# 9AxisCombo.net
KiCad netlist of a schematic drawn in EAGLE
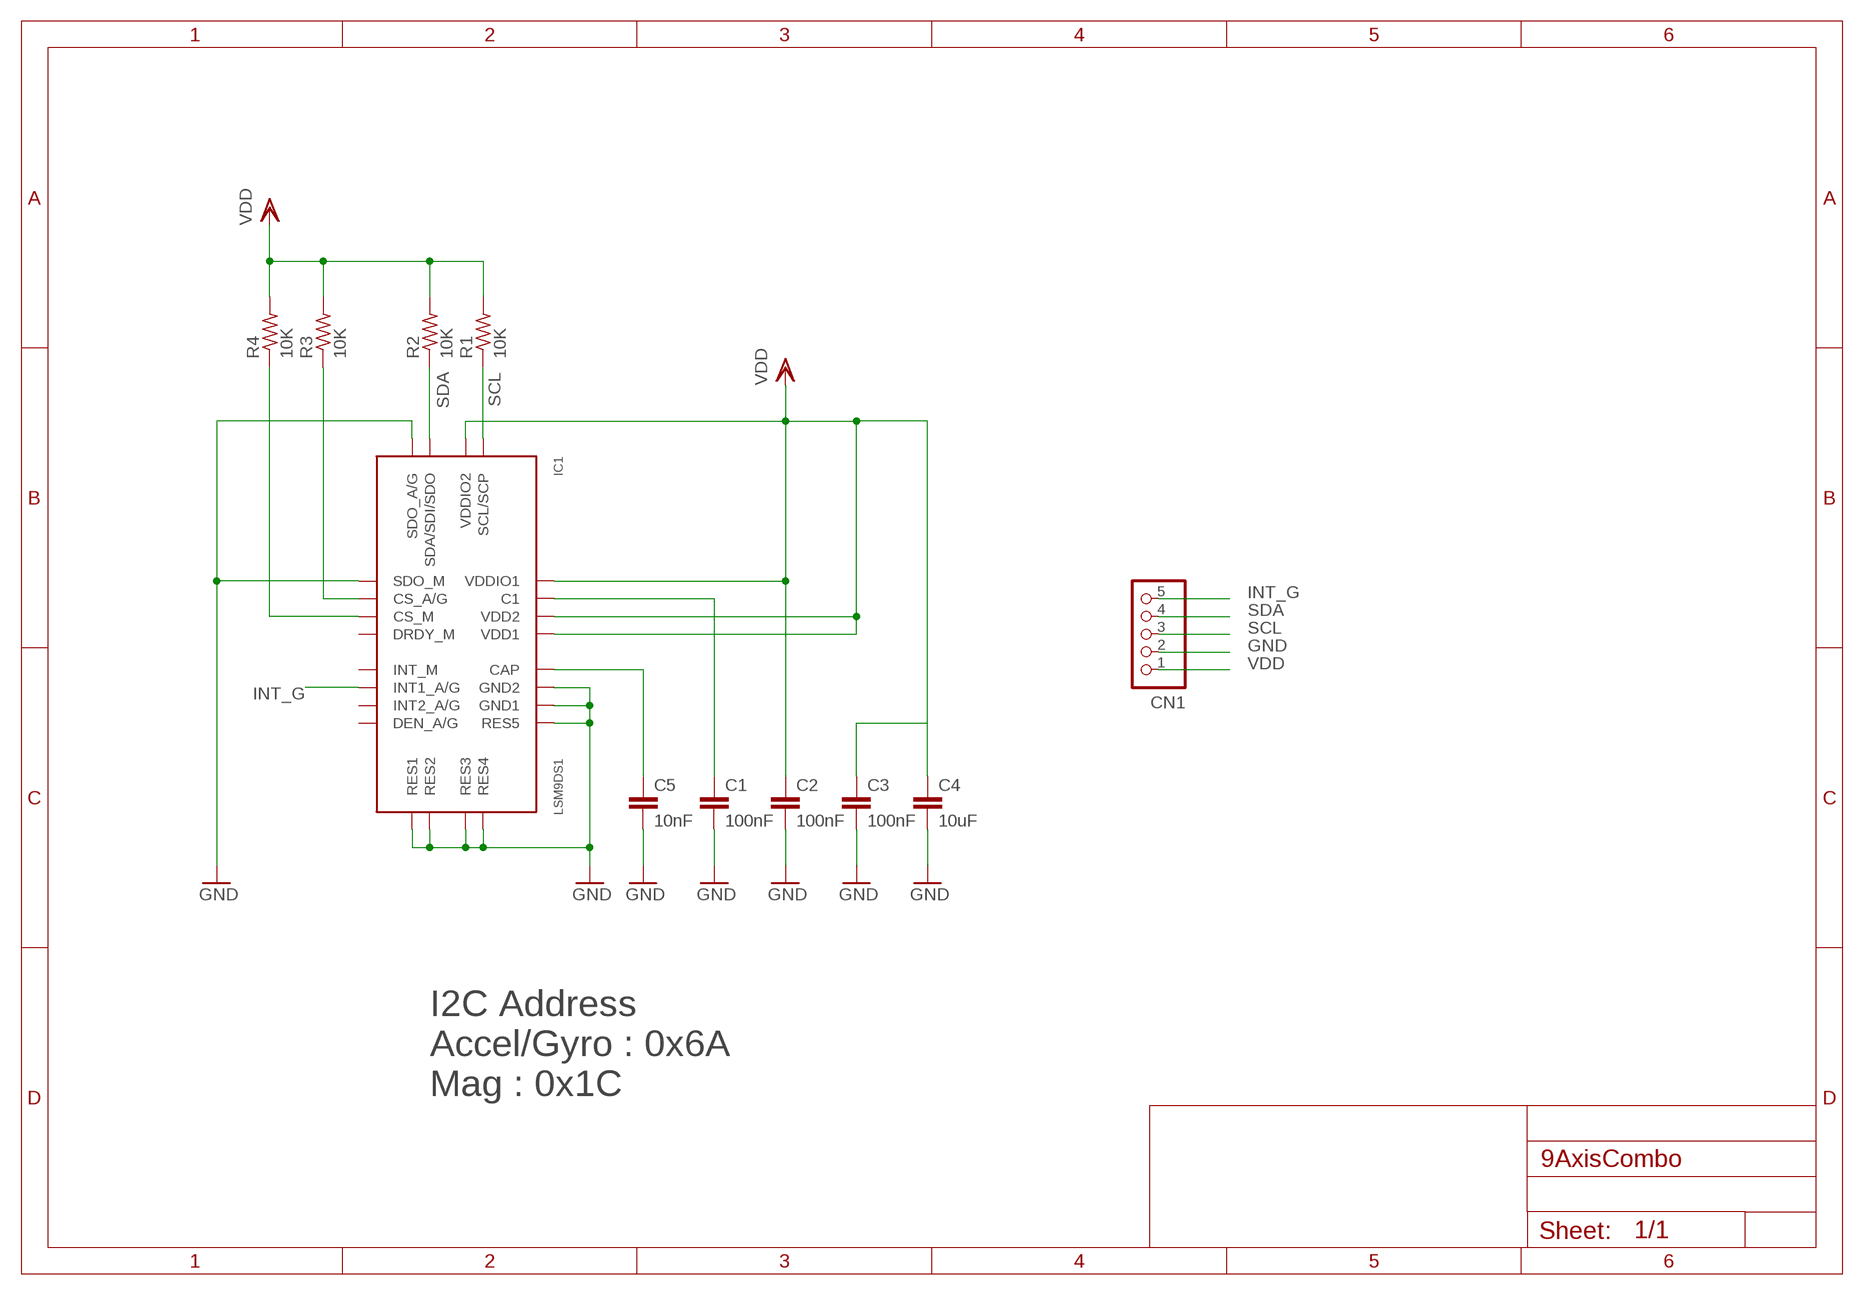
[diagram p0: schematic, sheet 1]

(export (version "E")
  (design (tool "Eeschema 10.0.6"))
  (components
    (comp (ref "C1")
      (value "100nF")
      (footprint "eagle-import:C0603")
      (libsource (lib "eagle-import") (part "C-EUC0603"))
    )
    (comp (ref "C2")
      (value "100nF")
      (footprint "eagle-import:C0603")
      (libsource (lib "eagle-import") (part "C-EUC0603"))
    )
    (comp (ref "C3")
      (value "100nF")
      (footprint "eagle-import:C0603")
      (libsource (lib "eagle-import") (part "C-EUC0603"))
    )
    (comp (ref "C4")
      (value "10uF")
      (footprint "eagle-import:C0603")
      (libsource (lib "eagle-import") (part "C-EUC0603"))
    )
    (comp (ref "C5")
      (value "10nF")
      (footprint "eagle-import:C0603")
      (libsource (lib "eagle-import") (part "C-EUC0603"))
    )
    (comp (ref "CN1")
      (value "B5B-PH-K-S")
      (footprint "eagle-import:B5B-PH-K-S")
      (libsource (lib "eagle-import") (part "B5B-PH-K-S"))
    )
    (comp (ref "IC1")
      (value "LSM9DS1")
      (footprint "eagle-import:LGA-24L")
      (libsource (lib "eagle-import") (part "LSM9DS1"))
    )
    (comp (ref "R1")
      (value "10K")
      (footprint "eagle-import:R0603")
      (libsource (lib "eagle-import") (part "R-US_R0603"))
    )
    (comp (ref "R2")
      (value "10K")
      (footprint "eagle-import:R0603")
      (libsource (lib "eagle-import") (part "R-US_R0603"))
    )
    (comp (ref "R3")
      (value "10K")
      (footprint "eagle-import:R0603")
      (libsource (lib "eagle-import") (part "R-US_R0603"))
    )
    (comp (ref "R4")
      (value "10K")
      (footprint "eagle-import:R0603")
      (libsource (lib "eagle-import") (part "R-US_R0603"))
    )
  )
  (nets
    (net (code "1") (name "/INT_G") (class "Default")
      (node (ref "CN1") (pin "5") (pinfunction "5_5") (pintype "passive"))
      (node (ref "IC1") (pin "11") (pinfunction "INT1_A/G_11") (pintype "bidirectional"))
    )
    (net (code "2") (name "/SCL") (class "Default")
      (node (ref "CN1") (pin "3") (pinfunction "3_3") (pintype "passive"))
      (node (ref "IC1") (pin "2") (pinfunction "SCL/SCP_2") (pintype "bidirectional"))
      (node (ref "R1") (pin "1") (pinfunction "1_1") (pintype "passive"))
    )
    (net (code "3") (name "/SDA") (class "Default")
      (node (ref "CN1") (pin "4") (pinfunction "4_4") (pintype "passive"))
      (node (ref "IC1") (pin "4") (pinfunction "SDA/SDI/SDO_4") (pintype "bidirectional"))
      (node (ref "R2") (pin "1") (pinfunction "1_1") (pintype "passive"))
    )
    (net (code "4") (name "GND") (class "Default")
      (node (ref "C1") (pin "2") (pinfunction "2_2") (pintype "passive"))
      (node (ref "C2") (pin "2") (pinfunction "2_2") (pintype "passive"))
      (node (ref "C3") (pin "2") (pinfunction "2_2") (pintype "passive"))
      (node (ref "C4") (pin "2") (pinfunction "2_2") (pintype "passive"))
      (node (ref "C5") (pin "2") (pinfunction "2_2") (pintype "passive"))
      (node (ref "CN1") (pin "2") (pinfunction "2_2") (pintype "passive"))
      (node (ref "IC1") (pin "14") (pinfunction "RES1_14") (pintype "bidirectional"))
      (node (ref "IC1") (pin "15") (pinfunction "RES2_15") (pintype "bidirectional"))
      (node (ref "IC1") (pin "16") (pinfunction "RES3_16") (pintype "bidirectional"))
      (node (ref "IC1") (pin "17") (pinfunction "RES4_17") (pintype "bidirectional"))
      (node (ref "IC1") (pin "18") (pinfunction "RES5_18") (pintype "bidirectional"))
      (node (ref "IC1") (pin "19") (pinfunction "GND1_19") (pintype "power_in"))
      (node (ref "IC1") (pin "20") (pinfunction "GND2_20") (pintype "power_in"))
      (node (ref "IC1") (pin "5") (pinfunction "SDO_A/G_5") (pintype "bidirectional"))
      (node (ref "IC1") (pin "6") (pinfunction "SDO_M_6") (pintype "bidirectional"))
    )
    (net (code "5") (name "Net-(IC1-C1)") (class "Default")
      (node (ref "C1") (pin "1") (pinfunction "1_1") (pintype "passive"))
      (node (ref "IC1") (pin "24") (pinfunction "C1_24") (pintype "power_in"))
    )
    (net (code "6") (name "Net-(IC1-CAP)") (class "Default")
      (node (ref "C5") (pin "1") (pinfunction "1_1") (pintype "passive"))
      (node (ref "IC1") (pin "21") (pinfunction "CAP_21") (pintype "power_in"))
    )
    (net (code "7") (name "Net-(IC1-CS_A{slash}G)") (class "Default")
      (node (ref "IC1") (pin "7") (pinfunction "CS_A/G_7") (pintype "bidirectional"))
      (node (ref "R3") (pin "1") (pinfunction "1_1") (pintype "passive"))
    )
    (net (code "8") (name "Net-(IC1-CS_M)") (class "Default")
      (node (ref "IC1") (pin "8") (pinfunction "CS_M_8") (pintype "bidirectional"))
      (node (ref "R4") (pin "1") (pinfunction "1_1") (pintype "passive"))
    )
    (net (code "9") (name "VDD") (class "Default")
      (node (ref "C2") (pin "1") (pinfunction "1_1") (pintype "passive"))
      (node (ref "C4") (pin "1") (pinfunction "1_1") (pintype "passive"))
      (node (ref "CN1") (pin "1") (pinfunction "1_1") (pintype "passive"))
      (node (ref "IC1") (pin "1") (pinfunction "VDDIO1_1") (pintype "power_in"))
      (node (ref "IC1") (pin "22") (pinfunction "VDD1_22") (pintype "power_in"))
      (node (ref "IC1") (pin "23") (pinfunction "VDD2_23") (pintype "power_in"))
      (node (ref "IC1") (pin "3") (pinfunction "VDDIO2_3") (pintype "power_in"))
      (node (ref "R1") (pin "2") (pinfunction "2_2") (pintype "passive"))
      (node (ref "R2") (pin "2") (pinfunction "2_2") (pintype "passive"))
      (node (ref "R3") (pin "2") (pinfunction "2_2") (pintype "passive"))
      (node (ref "R4") (pin "2") (pinfunction "2_2") (pintype "passive"))
    )
    (net (code "10") (name "unconnected-(C3-Pad1)") (class "Default")
      (node (ref "C3") (pin "1") (pinfunction "1_1") (pintype "passive"))
    )
    (net (code "11") (name "unconnected-(IC1-DEN_A{slash}G-Pad13)") (class "Default")
      (node (ref "IC1") (pin "13") (pinfunction "DEN_A/G_13") (pintype "bidirectional"))
    )
    (net (code "12") (name "unconnected-(IC1-DRDY_M-Pad9)") (class "Default")
      (node (ref "IC1") (pin "9") (pinfunction "DRDY_M_9") (pintype "bidirectional"))
    )
    (net (code "13") (name "unconnected-(IC1-INT2_A{slash}G-Pad12)") (class "Default")
      (node (ref "IC1") (pin "12") (pinfunction "INT2_A/G_12") (pintype "bidirectional"))
    )
    (net (code "14") (name "unconnected-(IC1-INT_M-Pad10)") (class "Default")
      (node (ref "IC1") (pin "10") (pinfunction "INT_M_10") (pintype "bidirectional"))
    )
  )
)
